# scr.net
KiCad netlist of a schematic drawn in EAGLE
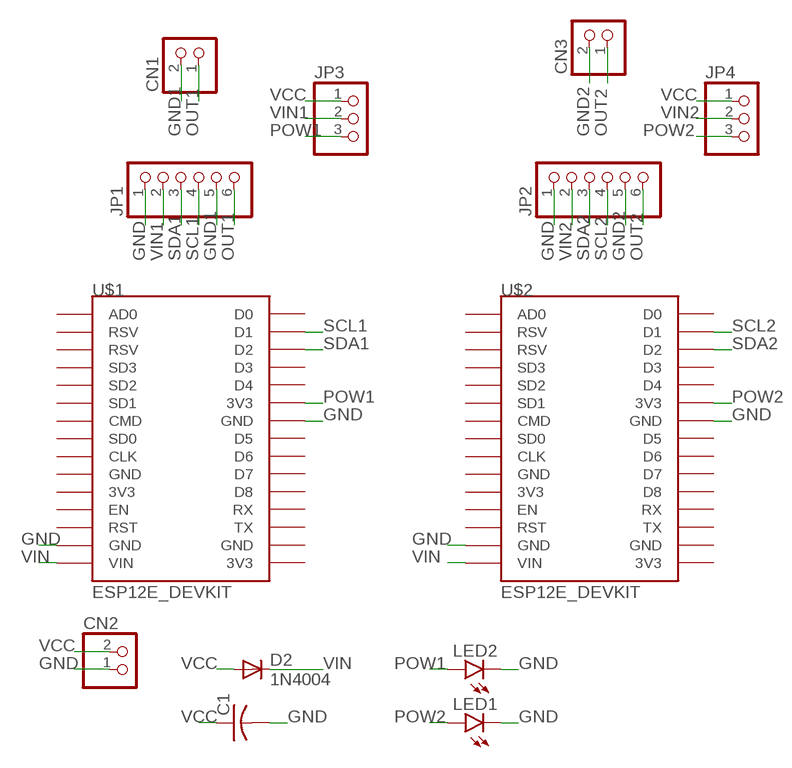
[diagram p0: schematic, sheet 1]

(export (version "E")
  (design (tool "Eeschema 10.0.6"))
  (components
    (comp (ref "C1")
      (value "C-US025-040X050")
      (footprint "eagle-import:C025-040X050")
      (libsource (lib "eagle-import") (part "C-US025-040X050"))
    )
    (comp (ref "CN1")
      (value "JST_2PIN-THM")
      (footprint "eagle-import:JST-PH-2-THM")
      (libsource (lib "eagle-import") (part "JST_2PIN-THM"))
    )
    (comp (ref "CN2")
      (value "JST_2PIN-THM")
      (footprint "eagle-import:JST-PH-2-THM")
      (libsource (lib "eagle-import") (part "JST_2PIN-THM"))
    )
    (comp (ref "CN3")
      (value "JST_2PIN-THM")
      (footprint "eagle-import:JST-PH-2-THM")
      (libsource (lib "eagle-import") (part "JST_2PIN-THM"))
    )
    (comp (ref "D2")
      (value "1N4004")
      (footprint "eagle-import:DO41-10")
      (libsource (lib "eagle-import") (part "1N4004"))
    )
    (comp (ref "JP1")
      (value "PINHD-1X6")
      (footprint "eagle-import:1X06")
      (libsource (lib "eagle-import") (part "PINHD-1X6"))
    )
    (comp (ref "JP2")
      (value "PINHD-1X6")
      (footprint "eagle-import:1X06")
      (libsource (lib "eagle-import") (part "PINHD-1X6"))
    )
    (comp (ref "JP3")
      (value "PINHD-1X3CB")
      (footprint "eagle-import:1X03-CLEANBIG")
      (libsource (lib "eagle-import") (part "PINHD-1X3CB"))
    )
    (comp (ref "JP4")
      (value "PINHD-1X3CB")
      (footprint "eagle-import:1X03-CLEANBIG")
      (libsource (lib "eagle-import") (part "PINHD-1X3CB"))
    )
    (comp (ref "LED1")
      (value "LED5MM")
      (footprint "eagle-import:LED5MM")
      (libsource (lib "eagle-import") (part "LED5MM"))
    )
    (comp (ref "LED2")
      (value "LED5MM")
      (footprint "eagle-import:LED5MM")
      (libsource (lib "eagle-import") (part "LED5MM"))
    )
    (comp (ref "U$1")
      (value "ESP12E_DEVKIT")
      (footprint "eagle-import:ESP12E_DEVKIT")
      (libsource (lib "eagle-import") (part "ESP12E_DEVKIT"))
    )
    (comp (ref "U$2")
      (value "ESP12E_DEVKIT")
      (footprint "eagle-import:ESP12E_DEVKIT")
      (libsource (lib "eagle-import") (part "ESP12E_DEVKIT"))
    )
  )
  (nets
    (net (code "1") (name "/GND") (class "Default")
      (node (ref "C1") (pin "2") (pinfunction "2_2") (pintype "passive"))
      (node (ref "CN2") (pin "1") (pinfunction "2_1") (pintype "passive"))
      (node (ref "JP1") (pin "1") (pinfunction "1_1") (pintype "passive"))
      (node (ref "JP2") (pin "1") (pinfunction "1_1") (pintype "passive"))
      (node (ref "LED1") (pin "K") (pinfunction "C_K") (pintype "passive"))
      (node (ref "LED2") (pin "K") (pinfunction "C_K") (pintype "passive"))
      (node (ref "U$1") (pin "GND@1") (pinfunction "GND_GND@1") (pintype "bidirectional"))
      (node (ref "U$1") (pin "GND@2") (pinfunction "GND_GND@2") (pintype "bidirectional"))
      (node (ref "U$2") (pin "GND@1") (pinfunction "GND_GND@1") (pintype "bidirectional"))
      (node (ref "U$2") (pin "GND@2") (pinfunction "GND_GND@2") (pintype "bidirectional"))
    )
    (net (code "2") (name "/GND1") (class "Default")
      (node (ref "CN1") (pin "2") (pinfunction "1_2") (pintype "passive"))
      (node (ref "JP1") (pin "5") (pinfunction "5_5") (pintype "passive"))
    )
    (net (code "3") (name "/GND2") (class "Default")
      (node (ref "CN3") (pin "2") (pinfunction "1_2") (pintype "passive"))
      (node (ref "JP2") (pin "5") (pinfunction "5_5") (pintype "passive"))
    )
    (net (code "4") (name "/OUT1") (class "Default")
      (node (ref "CN1") (pin "1") (pinfunction "2_1") (pintype "passive"))
      (node (ref "JP1") (pin "6") (pinfunction "6_6") (pintype "passive"))
    )
    (net (code "5") (name "/OUT2") (class "Default")
      (node (ref "CN3") (pin "1") (pinfunction "2_1") (pintype "passive"))
      (node (ref "JP2") (pin "6") (pinfunction "6_6") (pintype "passive"))
    )
    (net (code "6") (name "/POW1") (class "Default")
      (node (ref "JP3") (pin "3") (pinfunction "3_3") (pintype "passive"))
      (node (ref "LED2") (pin "A") (pinfunction "A_A") (pintype "passive"))
      (node (ref "U$1") (pin "3V3@1") (pinfunction "3V3_3V3@1") (pintype "bidirectional"))
    )
    (net (code "7") (name "/POW2") (class "Default")
      (node (ref "JP4") (pin "3") (pinfunction "3_3") (pintype "passive"))
      (node (ref "LED1") (pin "A") (pinfunction "A_A") (pintype "passive"))
      (node (ref "U$2") (pin "3V3@1") (pinfunction "3V3_3V3@1") (pintype "bidirectional"))
    )
    (net (code "8") (name "/SCL1") (class "Default")
      (node (ref "JP1") (pin "4") (pinfunction "4_4") (pintype "passive"))
      (node (ref "U$1") (pin "D1") (pinfunction "D1_D1") (pintype "bidirectional"))
    )
    (net (code "9") (name "/SCL2") (class "Default")
      (node (ref "JP2") (pin "4") (pinfunction "4_4") (pintype "passive"))
      (node (ref "U$2") (pin "D1") (pinfunction "D1_D1") (pintype "bidirectional"))
    )
    (net (code "10") (name "/SDA1") (class "Default")
      (node (ref "JP1") (pin "3") (pinfunction "3_3") (pintype "passive"))
      (node (ref "U$1") (pin "D2") (pinfunction "D2_D2") (pintype "bidirectional"))
    )
    (net (code "11") (name "/SDA2") (class "Default")
      (node (ref "JP2") (pin "3") (pinfunction "3_3") (pintype "passive"))
      (node (ref "U$2") (pin "D2") (pinfunction "D2_D2") (pintype "bidirectional"))
    )
    (net (code "12") (name "/VCC") (class "Default")
      (node (ref "C1") (pin "1") (pinfunction "1_1") (pintype "passive"))
      (node (ref "CN2") (pin "2") (pinfunction "1_2") (pintype "passive"))
      (node (ref "D2") (pin "A") (pinfunction "A_A") (pintype "passive"))
      (node (ref "JP3") (pin "1") (pinfunction "1_1") (pintype "passive"))
      (node (ref "JP4") (pin "1") (pinfunction "1_1") (pintype "passive"))
    )
    (net (code "13") (name "/VIN") (class "Default")
      (node (ref "D2") (pin "C") (pinfunction "C_C") (pintype "passive"))
      (node (ref "U$1") (pin "VIN") (pinfunction "VIN_VIN") (pintype "bidirectional"))
      (node (ref "U$2") (pin "VIN") (pinfunction "VIN_VIN") (pintype "bidirectional"))
    )
    (net (code "14") (name "/VIN1") (class "Default")
      (node (ref "JP1") (pin "2") (pinfunction "2_2") (pintype "passive"))
      (node (ref "JP3") (pin "2") (pinfunction "2_2") (pintype "passive"))
    )
    (net (code "15") (name "/VIN2") (class "Default")
      (node (ref "JP2") (pin "2") (pinfunction "2_2") (pintype "passive"))
      (node (ref "JP4") (pin "2") (pinfunction "2_2") (pintype "passive"))
    )
    (net (code "16") (name "unconnected-(U$1-3V3-Pad3V3@0)") (class "Default")
      (node (ref "U$1") (pin "3V3@0") (pinfunction "3V3_3V3@0") (pintype "bidirectional"))
    )
    (net (code "17") (name "unconnected-(U$1-3V3-Pad3V3@2)") (class "Default")
      (node (ref "U$1") (pin "3V3@2") (pinfunction "3V3_3V3@2") (pintype "bidirectional"))
    )
    (net (code "18") (name "unconnected-(U$1-GND-PadGND@0)") (class "Default")
      (node (ref "U$1") (pin "GND@0") (pinfunction "GND_GND@0") (pintype "bidirectional"))
    )
    (net (code "19") (name "unconnected-(U$1-GND-PadGND@3)") (class "Default")
      (node (ref "U$1") (pin "GND@3") (pinfunction "GND_GND@3") (pintype "bidirectional"))
    )
    (net (code "20") (name "unconnected-(U$1-PadAD0)") (class "Default")
      (node (ref "U$1") (pin "AD0") (pinfunction "AD0_AD0") (pintype "bidirectional"))
    )
    (net (code "21") (name "unconnected-(U$1-PadCLK)") (class "Default")
      (node (ref "U$1") (pin "CLK") (pinfunction "CLK_CLK") (pintype "bidirectional"))
    )
    (net (code "22") (name "unconnected-(U$1-PadCMD)") (class "Default")
      (node (ref "U$1") (pin "CMD") (pinfunction "CMD_CMD") (pintype "bidirectional"))
    )
    (net (code "23") (name "unconnected-(U$1-PadD0)") (class "Default")
      (node (ref "U$1") (pin "D0") (pinfunction "D0_D0") (pintype "bidirectional"))
    )
    (net (code "24") (name "unconnected-(U$1-PadD3)") (class "Default")
      (node (ref "U$1") (pin "D3") (pinfunction "D3_D3") (pintype "bidirectional"))
    )
    (net (code "25") (name "unconnected-(U$1-PadD4)") (class "Default")
      (node (ref "U$1") (pin "D4") (pinfunction "D4_D4") (pintype "bidirectional"))
    )
    (net (code "26") (name "unconnected-(U$1-PadD5)") (class "Default")
      (node (ref "U$1") (pin "D5") (pinfunction "D5_D5") (pintype "bidirectional"))
    )
    (net (code "27") (name "unconnected-(U$1-PadD6)") (class "Default")
      (node (ref "U$1") (pin "D6") (pinfunction "D6_D6") (pintype "bidirectional"))
    )
    (net (code "28") (name "unconnected-(U$1-PadD7)") (class "Default")
      (node (ref "U$1") (pin "D7") (pinfunction "D7_D7") (pintype "bidirectional"))
    )
    (net (code "29") (name "unconnected-(U$1-PadD8)") (class "Default")
      (node (ref "U$1") (pin "D8") (pinfunction "D8_D8") (pintype "bidirectional"))
    )
    (net (code "30") (name "unconnected-(U$1-PadEN)") (class "Default")
      (node (ref "U$1") (pin "EN") (pinfunction "EN_EN") (pintype "bidirectional"))
    )
    (net (code "31") (name "unconnected-(U$1-PadRST)") (class "Default")
      (node (ref "U$1") (pin "RST") (pinfunction "RST_RST") (pintype "bidirectional"))
    )
    (net (code "32") (name "unconnected-(U$1-PadRX)") (class "Default")
      (node (ref "U$1") (pin "RX") (pinfunction "RX_RX") (pintype "bidirectional"))
    )
    (net (code "33") (name "unconnected-(U$1-PadSD0)") (class "Default")
      (node (ref "U$1") (pin "SD0") (pinfunction "SD0_SD0") (pintype "bidirectional"))
    )
    (net (code "34") (name "unconnected-(U$1-PadSD1)") (class "Default")
      (node (ref "U$1") (pin "SD1") (pinfunction "SD1_SD1") (pintype "bidirectional"))
    )
    (net (code "35") (name "unconnected-(U$1-PadSD2)") (class "Default")
      (node (ref "U$1") (pin "SD2") (pinfunction "SD2_SD2") (pintype "bidirectional"))
    )
    (net (code "36") (name "unconnected-(U$1-PadSD3)") (class "Default")
      (node (ref "U$1") (pin "SD3") (pinfunction "SD3_SD3") (pintype "bidirectional"))
    )
    (net (code "37") (name "unconnected-(U$1-PadTX)") (class "Default")
      (node (ref "U$1") (pin "TX") (pinfunction "TX_TX") (pintype "bidirectional"))
    )
    (net (code "38") (name "unconnected-(U$1-RSV-PadRSV@0)") (class "Default")
      (node (ref "U$1") (pin "RSV@0") (pinfunction "RSV_RSV@0") (pintype "bidirectional"))
    )
    (net (code "39") (name "unconnected-(U$1-RSV-PadRSV@1)") (class "Default")
      (node (ref "U$1") (pin "RSV@1") (pinfunction "RSV_RSV@1") (pintype "bidirectional"))
    )
    (net (code "40") (name "unconnected-(U$2-3V3-Pad3V3@0)") (class "Default")
      (node (ref "U$2") (pin "3V3@0") (pinfunction "3V3_3V3@0") (pintype "bidirectional"))
    )
    (net (code "41") (name "unconnected-(U$2-3V3-Pad3V3@2)") (class "Default")
      (node (ref "U$2") (pin "3V3@2") (pinfunction "3V3_3V3@2") (pintype "bidirectional"))
    )
    (net (code "42") (name "unconnected-(U$2-GND-PadGND@0)") (class "Default")
      (node (ref "U$2") (pin "GND@0") (pinfunction "GND_GND@0") (pintype "bidirectional"))
    )
    (net (code "43") (name "unconnected-(U$2-GND-PadGND@3)") (class "Default")
      (node (ref "U$2") (pin "GND@3") (pinfunction "GND_GND@3") (pintype "bidirectional"))
    )
    (net (code "44") (name "unconnected-(U$2-PadAD0)") (class "Default")
      (node (ref "U$2") (pin "AD0") (pinfunction "AD0_AD0") (pintype "bidirectional"))
    )
    (net (code "45") (name "unconnected-(U$2-PadCLK)") (class "Default")
      (node (ref "U$2") (pin "CLK") (pinfunction "CLK_CLK") (pintype "bidirectional"))
    )
    (net (code "46") (name "unconnected-(U$2-PadCMD)") (class "Default")
      (node (ref "U$2") (pin "CMD") (pinfunction "CMD_CMD") (pintype "bidirectional"))
    )
    (net (code "47") (name "unconnected-(U$2-PadD0)") (class "Default")
      (node (ref "U$2") (pin "D0") (pinfunction "D0_D0") (pintype "bidirectional"))
    )
    (net (code "48") (name "unconnected-(U$2-PadD3)") (class "Default")
      (node (ref "U$2") (pin "D3") (pinfunction "D3_D3") (pintype "bidirectional"))
    )
    (net (code "49") (name "unconnected-(U$2-PadD4)") (class "Default")
      (node (ref "U$2") (pin "D4") (pinfunction "D4_D4") (pintype "bidirectional"))
    )
    (net (code "50") (name "unconnected-(U$2-PadD5)") (class "Default")
      (node (ref "U$2") (pin "D5") (pinfunction "D5_D5") (pintype "bidirectional"))
    )
    (net (code "51") (name "unconnected-(U$2-PadD6)") (class "Default")
      (node (ref "U$2") (pin "D6") (pinfunction "D6_D6") (pintype "bidirectional"))
    )
    (net (code "52") (name "unconnected-(U$2-PadD7)") (class "Default")
      (node (ref "U$2") (pin "D7") (pinfunction "D7_D7") (pintype "bidirectional"))
    )
    (net (code "53") (name "unconnected-(U$2-PadD8)") (class "Default")
      (node (ref "U$2") (pin "D8") (pinfunction "D8_D8") (pintype "bidirectional"))
    )
    (net (code "54") (name "unconnected-(U$2-PadEN)") (class "Default")
      (node (ref "U$2") (pin "EN") (pinfunction "EN_EN") (pintype "bidirectional"))
    )
    (net (code "55") (name "unconnected-(U$2-PadRST)") (class "Default")
      (node (ref "U$2") (pin "RST") (pinfunction "RST_RST") (pintype "bidirectional"))
    )
    (net (code "56") (name "unconnected-(U$2-PadRX)") (class "Default")
      (node (ref "U$2") (pin "RX") (pinfunction "RX_RX") (pintype "bidirectional"))
    )
    (net (code "57") (name "unconnected-(U$2-PadSD0)") (class "Default")
      (node (ref "U$2") (pin "SD0") (pinfunction "SD0_SD0") (pintype "bidirectional"))
    )
    (net (code "58") (name "unconnected-(U$2-PadSD1)") (class "Default")
      (node (ref "U$2") (pin "SD1") (pinfunction "SD1_SD1") (pintype "bidirectional"))
    )
    (net (code "59") (name "unconnected-(U$2-PadSD2)") (class "Default")
      (node (ref "U$2") (pin "SD2") (pinfunction "SD2_SD2") (pintype "bidirectional"))
    )
    (net (code "60") (name "unconnected-(U$2-PadSD3)") (class "Default")
      (node (ref "U$2") (pin "SD3") (pinfunction "SD3_SD3") (pintype "bidirectional"))
    )
    (net (code "61") (name "unconnected-(U$2-PadTX)") (class "Default")
      (node (ref "U$2") (pin "TX") (pinfunction "TX_TX") (pintype "bidirectional"))
    )
    (net (code "62") (name "unconnected-(U$2-RSV-PadRSV@0)") (class "Default")
      (node (ref "U$2") (pin "RSV@0") (pinfunction "RSV_RSV@0") (pintype "bidirectional"))
    )
    (net (code "63") (name "unconnected-(U$2-RSV-PadRSV@1)") (class "Default")
      (node (ref "U$2") (pin "RSV@1") (pinfunction "RSV_RSV@1") (pintype "bidirectional"))
    )
  )
)
